# DC-DC.net
KiCad netlist of a schematic drawn in Altium Designer
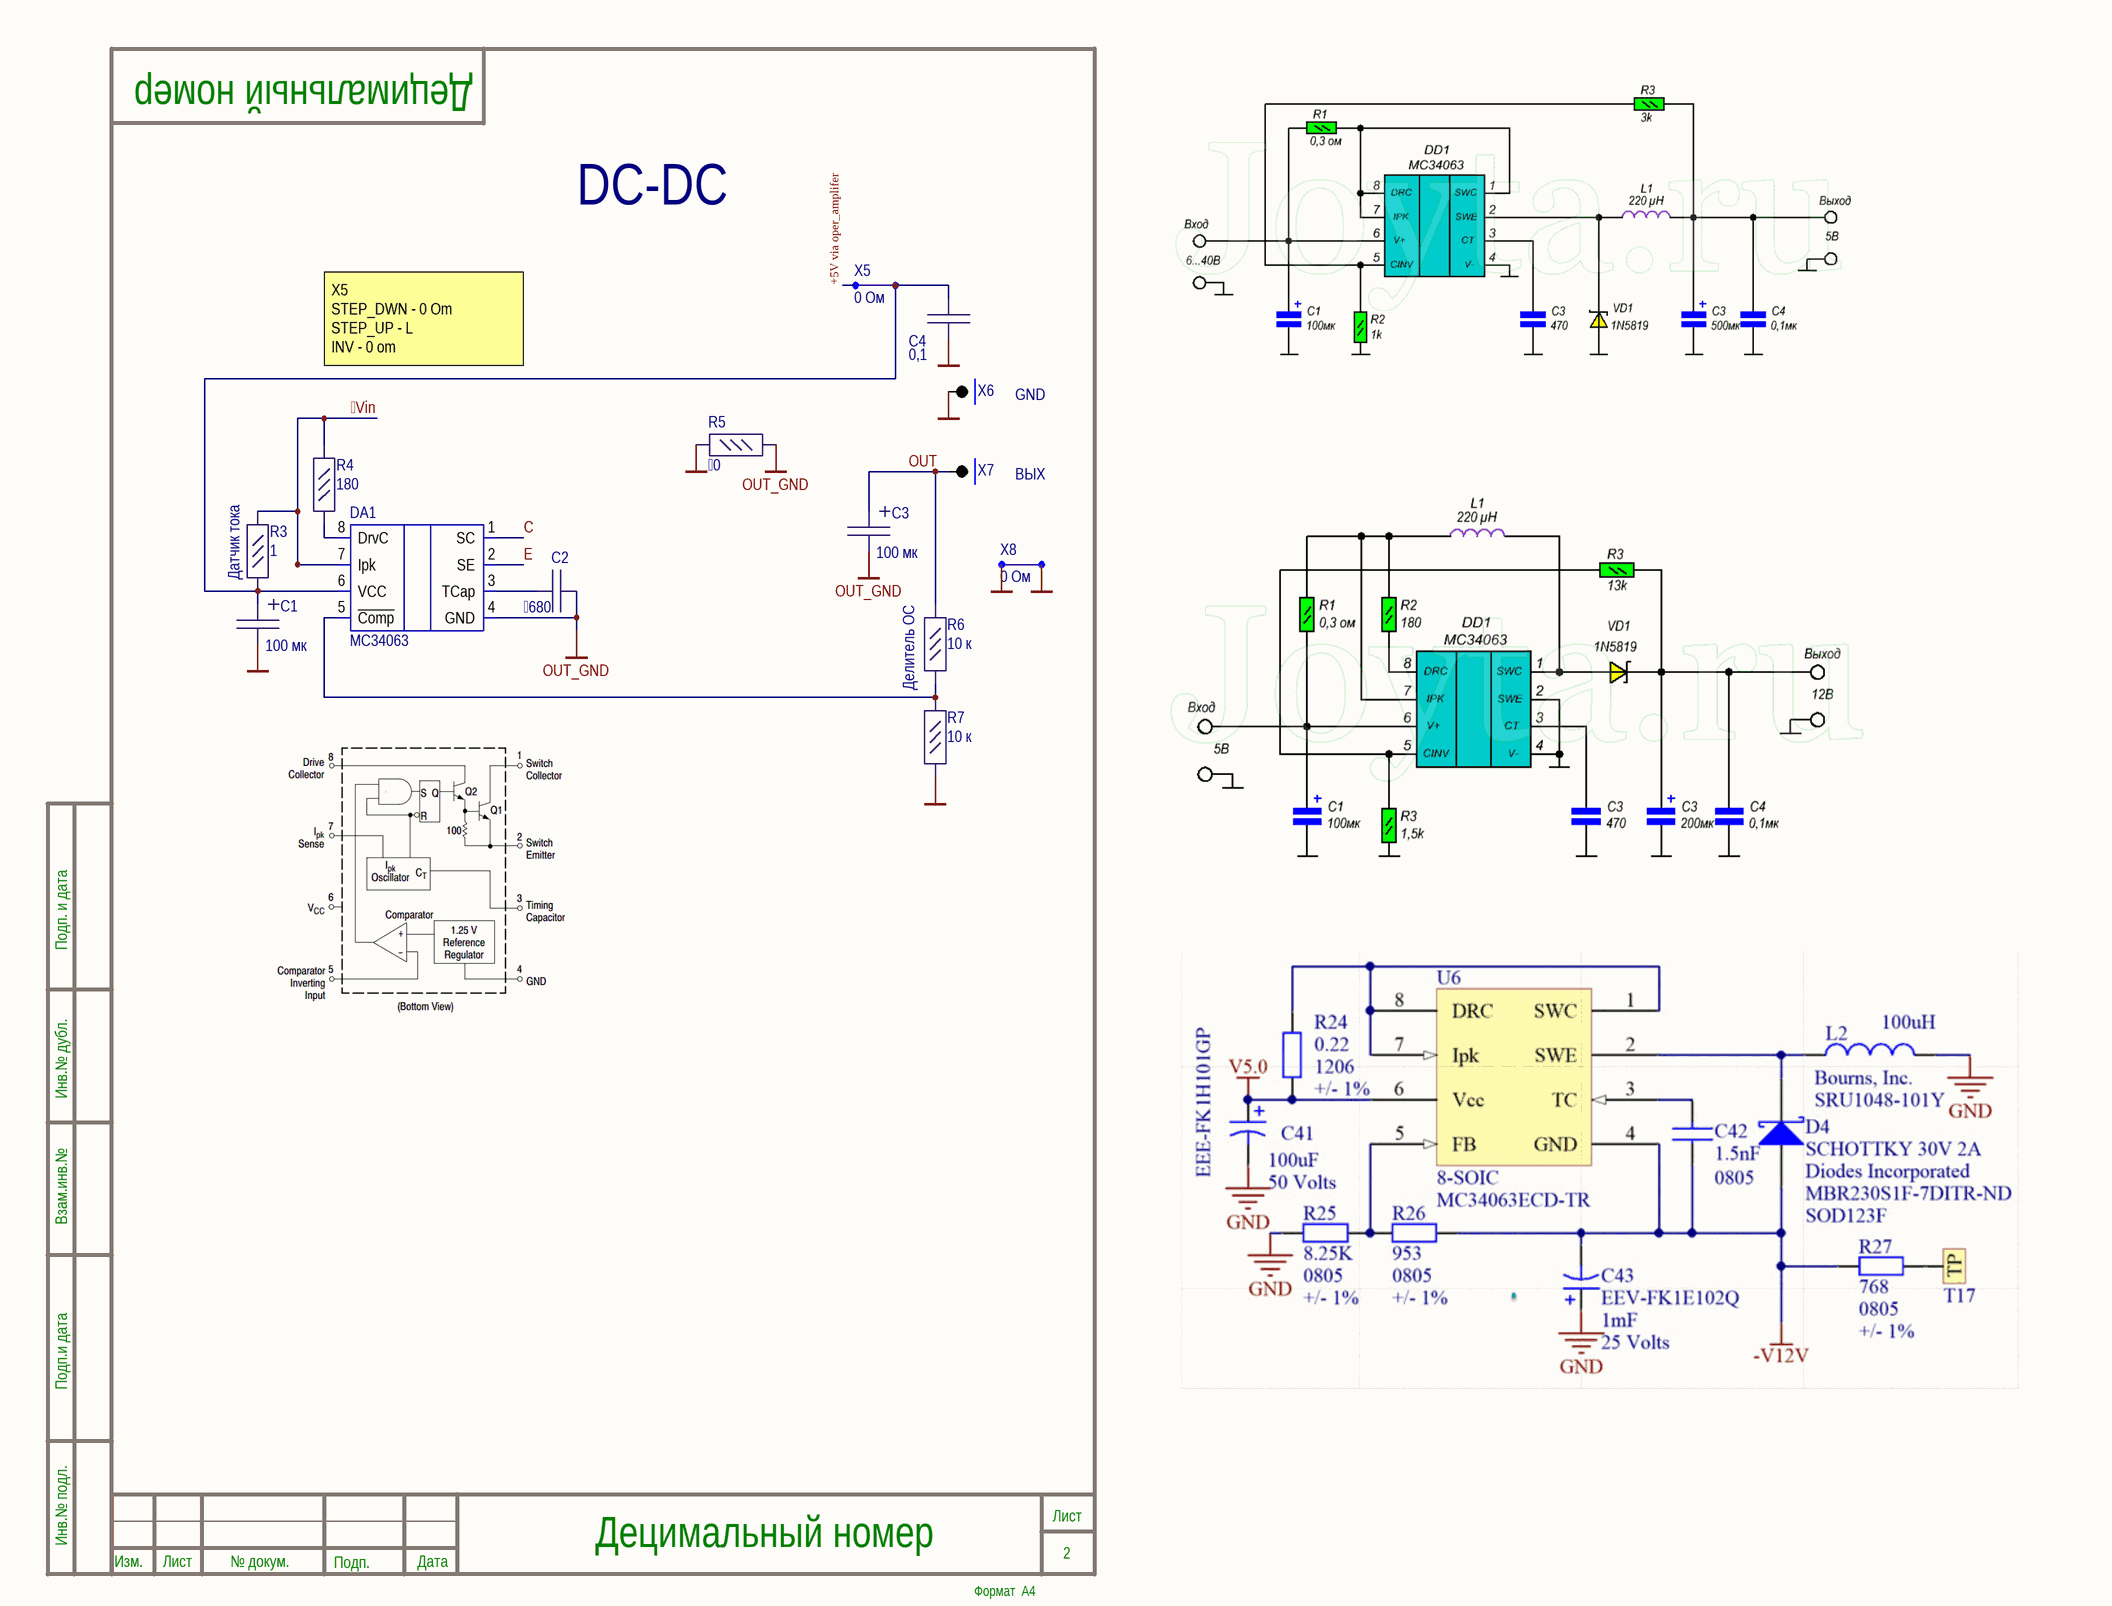
[diagram p0: DC-DC.SchDoc]

(export (version "E")
  (design (tool "Eeschema 10.0.6"))
  (components
    (comp (ref "C1")
      (value "100 мк")
      (footprint "User_Library:SMD_al_cap_0605_6.3")
      (description "CAP TANT 100UF 10% 4V 1411")
      (fields (field (name "PART NUMBER") "TAJB107K004RNJ") (field (name "MANUFACTURER") "AVX Corporation"))
      (libsource (lib "Database_Lib") (part "Tantalum Capacitor"))
    )
    (comp (ref "C2")
      (value "680")
      (footprint "2.Capasitors:C_0805")
      (description "CAP CER 0.1UF 100V X7R 0603")
      (fields
        (field (name "PART NUMBER") "GRM188R72A104KA35D")
        (field (name "MANUFACTURER") "Murata Electronics")
      )
      (libsource (lib "Database_Lib") (part "Capasitor"))
    )
    (comp (ref "C3")
      (value "100 мк")
      (footprint "User_Library:SMD_al_cap_0605_6.3")
      (description "CAP TANT 100UF 10% 4V 1411")
      (fields (field (name "PART NUMBER") "TAJB107K004RNJ") (field (name "MANUFACTURER") "AVX Corporation"))
      (libsource (lib "Database_Lib") (part "Tantalum Capacitor"))
    )
    (comp (ref "C4")
      (value "0,1")
      (footprint "PCB2:C_0805")
      (description "CAP CER 0.1UF 100V X7R 0603")
      (fields
        (field (name "PART NUMBER") "GRM188R72A104KA35D")
        (field (name "MANUFACTURER") "Murata Electronics")
      )
      (libsource (lib "Database_Lib") (part "Capasitor"))
    )
    (comp (ref "DA1") (value "MC34063") (footprint "SO-8") (libsource (lib "6.Chips") (part "MC34063")))
    (comp (ref "R3")
      (value "1")
      (footprint "1.Resistors:R_0805")
      (description "RES SMD 10K OHM 1% 1/10W 0603")
      (fields (field (name "PART NUMBER") "CR0603-FX-1002ELF") (field (name "MANUFACTURER") "Bourns Inc."))
      (libsource (lib "Database_Lib") (part "Resistor"))
    )
    (comp (ref "R4")
      (value "180")
      (footprint "1.Resistors:R_0805")
      (description "RES SMD 10K OHM 1% 1/10W 0603")
      (fields (field (name "PART NUMBER") "CR0603-FX-1002ELF") (field (name "MANUFACTURER") "Bourns Inc."))
      (libsource (lib "Database_Lib") (part "Resistor"))
    )
    (comp (ref "R5")
      (value "0")
      (footprint "1.Resistors:R_0805")
      (description "RES SMD 10K OHM 1% 1/10W 0603")
      (fields (field (name "PART NUMBER") "CR0603-FX-1002ELF") (field (name "MANUFACTURER") "Bourns Inc."))
      (libsource (lib "Database_Lib") (part "Resistor"))
    )
    (comp (ref "R6")
      (value "10 к")
      (footprint "1.Resistors:R_0805")
      (description "RES SMD 10K OHM 1% 1/10W 0603")
      (fields (field (name "PART NUMBER") "CR0603-FX-1002ELF") (field (name "MANUFACTURER") "Bourns Inc."))
      (libsource (lib "Database_Lib") (part "Resistor"))
    )
    (comp (ref "R7")
      (value "10 к")
      (footprint "1.Resistors:R_0805")
      (description "RES SMD 10K OHM 1% 1/10W 0603")
      (fields (field (name "PART NUMBER") "CR0603-FX-1002ELF") (field (name "MANUFACTURER") "Bourns Inc."))
      (libsource (lib "Database_Lib") (part "Resistor"))
    )
    (comp (ref "X5")
      (value "0 Ом")
      (footprint "User_Library:jumper")
      (libsource (lib "11.Other") (part "0 Ohm (0805)"))
    )
    (comp (ref "X6")
      (value "КТ")
      (footprint "User_Library:PLS-1")
      (libsource (lib "7.Connectors") (part "КТ"))
    )
    (comp (ref "X7")
      (value "КТ")
      (footprint "User_Library:PLS-1")
      (libsource (lib "7.Connectors") (part "КТ"))
    )
    (comp (ref "X8")
      (value "0 Ом")
      (footprint "User_Library:jumper")
      (libsource (lib "11.Other") (part "0 Ohm (0805)"))
    )
  )
  (nets
    (net (code "1") (name "/Vin") (class "Default")
      (node (ref "DA1") (pin "7") (pinfunction "Ipk_7") (pintype "passive"))
      (node (ref "R3") (pin "1") (pinfunction "1_1") (pintype "passive"))
      (node (ref "R4") (pin "1") (pinfunction "1_1") (pintype "passive"))
    )
    (net (code "2") (name "/+5V via oper_amplifer") (class "Default")
      (node (ref "X5") (pin "1") (pinfunction "1_1") (pintype "passive"))
    )
    (net (code "3") (name "/C") (class "Default")
      (node (ref "DA1") (pin "1") (pinfunction "SC_1") (pintype "passive"))
    )
    (net (code "4") (name "/E") (class "Default")
      (node (ref "DA1") (pin "2") (pinfunction "SE_2") (pintype "passive"))
    )
    (net (code "5") (name "/OUT") (class "Default")
      (node (ref "C3") (pin "1") (pinfunction "1_1") (pintype "passive"))
      (node (ref "R6") (pin "1") (pinfunction "1_1") (pintype "passive"))
      (node (ref "X7") (pin "1") (pinfunction "1_1") (pintype "passive"))
    )
    (net (code "6") (name "GND") (class "Default")
      (node (ref "C1") (pin "2") (pinfunction "2_2") (pintype "passive"))
      (node (ref "C4") (pin "2") (pinfunction "2_2") (pintype "passive"))
      (node (ref "R5") (pin "1") (pinfunction "1_1") (pintype "passive"))
      (node (ref "R7") (pin "2") (pinfunction "2_2") (pintype "passive"))
      (node (ref "X6") (pin "1") (pinfunction "1_1") (pintype "passive"))
      (node (ref "X8") (pin "1") (pinfunction "1_1") (pintype "passive"))
      (node (ref "X8") (pin "2") (pinfunction "2_2") (pintype "passive"))
    )
    (net (code "7") (name "Net-(DA1-DrvC)") (class "Default")
      (node (ref "DA1") (pin "8") (pinfunction "DrvC_8") (pintype "passive"))
      (node (ref "R4") (pin "2") (pinfunction "2_2") (pintype "passive"))
    )
    (net (code "8") (name "Net-(DA1-TCap)") (class "Default")
      (node (ref "C2") (pin "2") (pinfunction "2_2") (pintype "passive"))
      (node (ref "DA1") (pin "3") (pinfunction "TCap_3") (pintype "passive"))
    )
    (net (code "9") (name "Net-(DA1-VCC)") (class "Default")
      (node (ref "C1") (pin "1") (pinfunction "1_1") (pintype "passive"))
      (node (ref "C4") (pin "1") (pinfunction "1_1") (pintype "passive"))
      (node (ref "DA1") (pin "6") (pinfunction "VCC_6") (pintype "passive"))
      (node (ref "R3") (pin "2") (pinfunction "2_2") (pintype "passive"))
      (node (ref "X5") (pin "2") (pinfunction "2_2") (pintype "passive"))
    )
    (net (code "10") (name "Net-(DA1-~{Comp})") (class "Default")
      (node (ref "DA1") (pin "5") (pinfunction "~{Comp}_5") (pintype "passive"))
      (node (ref "R6") (pin "2") (pinfunction "2_2") (pintype "passive"))
      (node (ref "R7") (pin "1") (pinfunction "1_1") (pintype "passive"))
    )
    (net (code "11") (name "OUT_GND") (class "Default")
      (node (ref "C2") (pin "1") (pinfunction "1_1") (pintype "passive"))
      (node (ref "C3") (pin "2") (pinfunction "2_2") (pintype "passive"))
      (node (ref "DA1") (pin "4") (pinfunction "GND_4") (pintype "passive"))
      (node (ref "R5") (pin "2") (pinfunction "2_2") (pintype "passive"))
    )
  )
)
